# 2_Other.net
KiCad netlist of a schematic drawn in Altium Designer
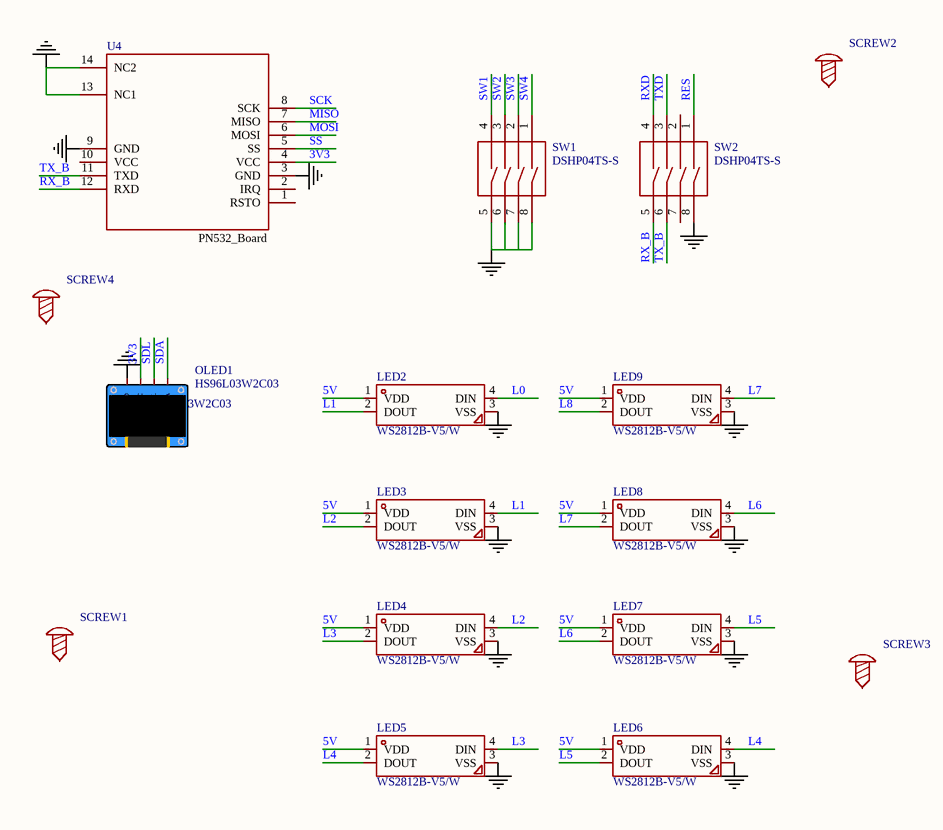
[diagram p0: 2_Other.schdoc]

(export (version "E")
  (design (tool "Eeschema 10.0.6"))
  (components
    (comp (ref "LED2")
      (value "WS2812B-V5/W")
      (description "无需外围元器件，有反接保护和过压保护，游乐设备，消费类电子，电竞领域，电脑周边及设备")
      (fields (field (name "MANUFACTURER") "worldsemi"))
      (libsource (lib "altium-import") (part "root_0_WS2812B-V5/W_"))
    )
    (comp (ref "LED3")
      (value "WS2812B-V5/W")
      (description "无需外围元器件，有反接保护和过压保护，游乐设备，消费类电子，电竞领域，电脑周边及设备")
      (fields (field (name "MANUFACTURER") "worldsemi"))
      (libsource (lib "altium-import") (part "root_0_WS2812B-V5/W_"))
    )
    (comp (ref "LED4")
      (value "WS2812B-V5/W")
      (description "无需外围元器件，有反接保护和过压保护，游乐设备，消费类电子，电竞领域，电脑周边及设备")
      (fields (field (name "MANUFACTURER") "worldsemi"))
      (libsource (lib "altium-import") (part "root_0_WS2812B-V5/W_"))
    )
    (comp (ref "LED5")
      (value "WS2812B-V5/W")
      (description "无需外围元器件，有反接保护和过压保护，游乐设备，消费类电子，电竞领域，电脑周边及设备")
      (fields (field (name "MANUFACTURER") "worldsemi"))
      (libsource (lib "altium-import") (part "root_0_WS2812B-V5/W_"))
    )
    (comp (ref "LED6")
      (value "WS2812B-V5/W")
      (description "无需外围元器件，有反接保护和过压保护，游乐设备，消费类电子，电竞领域，电脑周边及设备")
      (fields (field (name "MANUFACTURER") "worldsemi"))
      (libsource (lib "altium-import") (part "root_0_WS2812B-V5/W_"))
    )
    (comp (ref "LED7")
      (value "WS2812B-V5/W")
      (description "无需外围元器件，有反接保护和过压保护，游乐设备，消费类电子，电竞领域，电脑周边及设备")
      (fields (field (name "MANUFACTURER") "worldsemi"))
      (libsource (lib "altium-import") (part "root_0_WS2812B-V5/W_"))
    )
    (comp (ref "LED8")
      (value "WS2812B-V5/W")
      (description "无需外围元器件，有反接保护和过压保护，游乐设备，消费类电子，电竞领域，电脑周边及设备")
      (fields (field (name "MANUFACTURER") "worldsemi"))
      (libsource (lib "altium-import") (part "root_0_WS2812B-V5/W_"))
    )
    (comp (ref "LED9")
      (value "WS2812B-V5/W")
      (description "无需外围元器件，有反接保护和过压保护，游乐设备，消费类电子，电竞领域，电脑周边及设备")
      (fields (field (name "MANUFACTURER") "worldsemi"))
      (libsource (lib "altium-import") (part "root_0_WS2812B-V5/W_"))
    )
    (comp (ref "OLED1")
      (value "HS96L03W2C03")
      (description "主控芯片:SSD1315;接口类型:I2C;尺寸(inch):0.96;像素分辨率:128x64;")
      (fields (field (name "DEVICE") "HS96L03W2C03") (field (name "MANUFACTURER") "HS(汉昇)"))
      (libsource (lib "altium-import") (part "root_0_HS96L03W2C03_"))
    )
    (comp (ref "SCREW1") (value "M2螺丝") (libsource (lib "altium-import") (part "root_0_M2螺丝_")))
    (comp (ref "SCREW2") (value "M2螺丝") (libsource (lib "altium-import") (part "root_0_M2螺丝_")))
    (comp (ref "SCREW3") (value "M2螺丝") (libsource (lib "altium-import") (part "root_0_M2螺丝_")))
    (comp (ref "SCREW4") (value "M2螺丝") (libsource (lib "altium-import") (part "root_0_M2螺丝_")))
    (comp (ref "SW1")
      (value "DSHP04TS-S")
      (description "类型:平拨,凹槽式;电路结构:单刀单掷;开关位数:4位;额定电流:25mA;额定电压:24V;使用寿命:3千次;颜色:黑色;")
      (fields (field (name "MANUFACTURER") "XKB Connectivity(中国星坤)"))
      (libsource (lib "altium-import") (part "root_3_DSHP04TS-S_"))
    )
    (comp (ref "SW2")
      (value "DSHP04TS-S")
      (description "类型:平拨,凹槽式;电路结构:单刀单掷;开关位数:4位;额定电流:25mA;额定电压:24V;使用寿命:3千次;颜色:黑色;")
      (fields (field (name "MANUFACTURER") "XKB Connectivity(中国星坤)"))
      (libsource (lib "altium-import") (part "root_3_DSHP04TS-S_"))
    )
    (comp (ref "U4") (value "PN532_Board") (libsource (lib "altium-import") (part "root_0_PN532_Board_")))
  )
  (nets
    (net (code "1") (name "/3V3") (class "Default")
      (node (ref "OLED1") (pin "2") (pinfunction "VCC_2") (pintype "passive"))
      (node (ref "U4") (pin "4") (pinfunction "VCC_4") (pintype "passive"))
    )
    (net (code "2") (name "/5V") (class "Default")
      (node (ref "LED2") (pin "1") (pinfunction "VDD_1") (pintype "passive"))
      (node (ref "LED3") (pin "1") (pinfunction "VDD_1") (pintype "passive"))
      (node (ref "LED4") (pin "1") (pinfunction "VDD_1") (pintype "passive"))
      (node (ref "LED5") (pin "1") (pinfunction "VDD_1") (pintype "passive"))
      (node (ref "LED6") (pin "1") (pinfunction "VDD_1") (pintype "passive"))
      (node (ref "LED7") (pin "1") (pinfunction "VDD_1") (pintype "passive"))
      (node (ref "LED8") (pin "1") (pinfunction "VDD_1") (pintype "passive"))
      (node (ref "LED9") (pin "1") (pinfunction "VDD_1") (pintype "passive"))
    )
    (net (code "3") (name "/L0") (class "Default")
      (node (ref "LED2") (pin "4") (pinfunction "DIN_4") (pintype "passive"))
    )
    (net (code "4") (name "/L1") (class "Default")
      (node (ref "LED2") (pin "2") (pinfunction "DOUT_2") (pintype "passive"))
      (node (ref "LED3") (pin "4") (pinfunction "DIN_4") (pintype "passive"))
    )
    (net (code "5") (name "/L2") (class "Default")
      (node (ref "LED3") (pin "2") (pinfunction "DOUT_2") (pintype "passive"))
      (node (ref "LED4") (pin "4") (pinfunction "DIN_4") (pintype "passive"))
    )
    (net (code "6") (name "/L3") (class "Default")
      (node (ref "LED4") (pin "2") (pinfunction "DOUT_2") (pintype "passive"))
      (node (ref "LED5") (pin "4") (pinfunction "DIN_4") (pintype "passive"))
    )
    (net (code "7") (name "/L4") (class "Default")
      (node (ref "LED5") (pin "2") (pinfunction "DOUT_2") (pintype "passive"))
      (node (ref "LED6") (pin "4") (pinfunction "DIN_4") (pintype "passive"))
    )
    (net (code "8") (name "/L5") (class "Default")
      (node (ref "LED6") (pin "2") (pinfunction "DOUT_2") (pintype "passive"))
      (node (ref "LED7") (pin "4") (pinfunction "DIN_4") (pintype "passive"))
    )
    (net (code "9") (name "/L6") (class "Default")
      (node (ref "LED7") (pin "2") (pinfunction "DOUT_2") (pintype "passive"))
      (node (ref "LED8") (pin "4") (pinfunction "DIN_4") (pintype "passive"))
    )
    (net (code "10") (name "/L7") (class "Default")
      (node (ref "LED8") (pin "2") (pinfunction "DOUT_2") (pintype "passive"))
      (node (ref "LED9") (pin "4") (pinfunction "DIN_4") (pintype "passive"))
    )
    (net (code "11") (name "/L8") (class "Default")
      (node (ref "LED9") (pin "2") (pinfunction "DOUT_2") (pintype "passive"))
    )
    (net (code "12") (name "/MISO") (class "Default")
      (node (ref "U4") (pin "7") (pinfunction "MISO_7") (pintype "passive"))
    )
    (net (code "13") (name "/MOSI") (class "Default")
      (node (ref "U4") (pin "6") (pinfunction "MOSI_6") (pintype "passive"))
    )
    (net (code "14") (name "/RES") (class "Default")
      (node (ref "SW2") (pin "1") (pinfunction "1_1") (pintype "passive"))
    )
    (net (code "15") (name "/RXD") (class "Default")
      (node (ref "SW2") (pin "4") (pinfunction "4_4") (pintype "passive"))
    )
    (net (code "16") (name "/RX_B") (class "Default")
      (node (ref "SW2") (pin "5") (pinfunction "5_5") (pintype "passive"))
      (node (ref "U4") (pin "12") (pinfunction "RXD_12") (pintype "passive"))
    )
    (net (code "17") (name "/SCK") (class "Default")
      (node (ref "U4") (pin "8") (pinfunction "SCK_8") (pintype "passive"))
    )
    (net (code "18") (name "/SDA") (class "Default")
      (node (ref "OLED1") (pin "4") (pinfunction "SDA_4") (pintype "passive"))
    )
    (net (code "19") (name "/SDL") (class "Default")
      (node (ref "OLED1") (pin "3") (pinfunction "SCL_3") (pintype "passive"))
    )
    (net (code "20") (name "/SS") (class "Default")
      (node (ref "U4") (pin "5") (pinfunction "SS_5") (pintype "passive"))
    )
    (net (code "21") (name "/SW1") (class "Default")
      (node (ref "SW1") (pin "4") (pinfunction "4_4") (pintype "passive"))
    )
    (net (code "22") (name "/SW2") (class "Default")
      (node (ref "SW1") (pin "3") (pinfunction "3_3") (pintype "passive"))
    )
    (net (code "23") (name "/SW3") (class "Default")
      (node (ref "SW1") (pin "2") (pinfunction "2_2") (pintype "passive"))
    )
    (net (code "24") (name "/SW4") (class "Default")
      (node (ref "SW1") (pin "1") (pinfunction "1_1") (pintype "passive"))
    )
    (net (code "25") (name "/TXD") (class "Default")
      (node (ref "SW2") (pin "3") (pinfunction "3_3") (pintype "passive"))
    )
    (net (code "26") (name "/TX_B") (class "Default")
      (node (ref "SW2") (pin "6") (pinfunction "6_6") (pintype "passive"))
      (node (ref "U4") (pin "11") (pinfunction "TXD_11") (pintype "passive"))
    )
    (net (code "27") (name "GND") (class "Default")
      (node (ref "LED2") (pin "3") (pinfunction "VSS_3") (pintype "passive"))
      (node (ref "LED3") (pin "3") (pinfunction "VSS_3") (pintype "passive"))
      (node (ref "LED4") (pin "3") (pinfunction "VSS_3") (pintype "passive"))
      (node (ref "LED5") (pin "3") (pinfunction "VSS_3") (pintype "passive"))
      (node (ref "LED6") (pin "3") (pinfunction "VSS_3") (pintype "passive"))
      (node (ref "LED7") (pin "3") (pinfunction "VSS_3") (pintype "passive"))
      (node (ref "LED8") (pin "3") (pinfunction "VSS_3") (pintype "passive"))
      (node (ref "LED9") (pin "3") (pinfunction "VSS_3") (pintype "passive"))
      (node (ref "OLED1") (pin "1") (pinfunction "GND_1") (pintype "passive"))
      (node (ref "SW1") (pin "5") (pinfunction "5_5") (pintype "passive"))
      (node (ref "SW1") (pin "6") (pinfunction "6_6") (pintype "passive"))
      (node (ref "SW1") (pin "7") (pinfunction "7_7") (pintype "passive"))
      (node (ref "SW1") (pin "8") (pinfunction "8_8") (pintype "passive"))
      (node (ref "SW2") (pin "8") (pinfunction "8_8") (pintype "passive"))
      (node (ref "U4") (pin "13") (pinfunction "NC1_13") (pintype "passive"))
      (node (ref "U4") (pin "14") (pinfunction "NC2_14") (pintype "passive"))
      (node (ref "U4") (pin "3") (pinfunction "GND_3") (pintype "passive"))
      (node (ref "U4") (pin "9") (pinfunction "GND_9") (pintype "passive"))
    )
    (net (code "28") (name "unconnected-(SCREW1-Pad1)") (class "Default")
      (node (ref "SCREW1") (pin "1") (pinfunction "1_1") (pintype "passive"))
    )
    (net (code "29") (name "unconnected-(SCREW2-Pad1)") (class "Default")
      (node (ref "SCREW2") (pin "1") (pinfunction "1_1") (pintype "passive"))
    )
    (net (code "30") (name "unconnected-(SCREW3-Pad1)") (class "Default")
      (node (ref "SCREW3") (pin "1") (pinfunction "1_1") (pintype "passive"))
    )
    (net (code "31") (name "unconnected-(SCREW4-Pad1)") (class "Default")
      (node (ref "SCREW4") (pin "1") (pinfunction "1_1") (pintype "passive"))
    )
    (net (code "32") (name "unconnected-(SW2-Pad2)") (class "Default")
      (node (ref "SW2") (pin "2") (pinfunction "2_2") (pintype "passive"))
    )
    (net (code "33") (name "unconnected-(SW2-Pad7)") (class "Default")
      (node (ref "SW2") (pin "7") (pinfunction "7_7") (pintype "passive"))
    )
    (net (code "34") (name "unconnected-(U4-IRQ-Pad2)") (class "Default")
      (node (ref "U4") (pin "2") (pinfunction "IRQ_2") (pintype "passive"))
    )
    (net (code "35") (name "unconnected-(U4-RSTO-Pad1)") (class "Default")
      (node (ref "U4") (pin "1") (pinfunction "RSTO_1") (pintype "passive"))
    )
    (net (code "36") (name "unconnected-(U4-VCC-Pad10)") (class "Default")
      (node (ref "U4") (pin "10") (pinfunction "VCC_10") (pintype "passive"))
    )
  )
)
